# MotorControl.net
KiCad netlist of a schematic drawn in Altium Designer
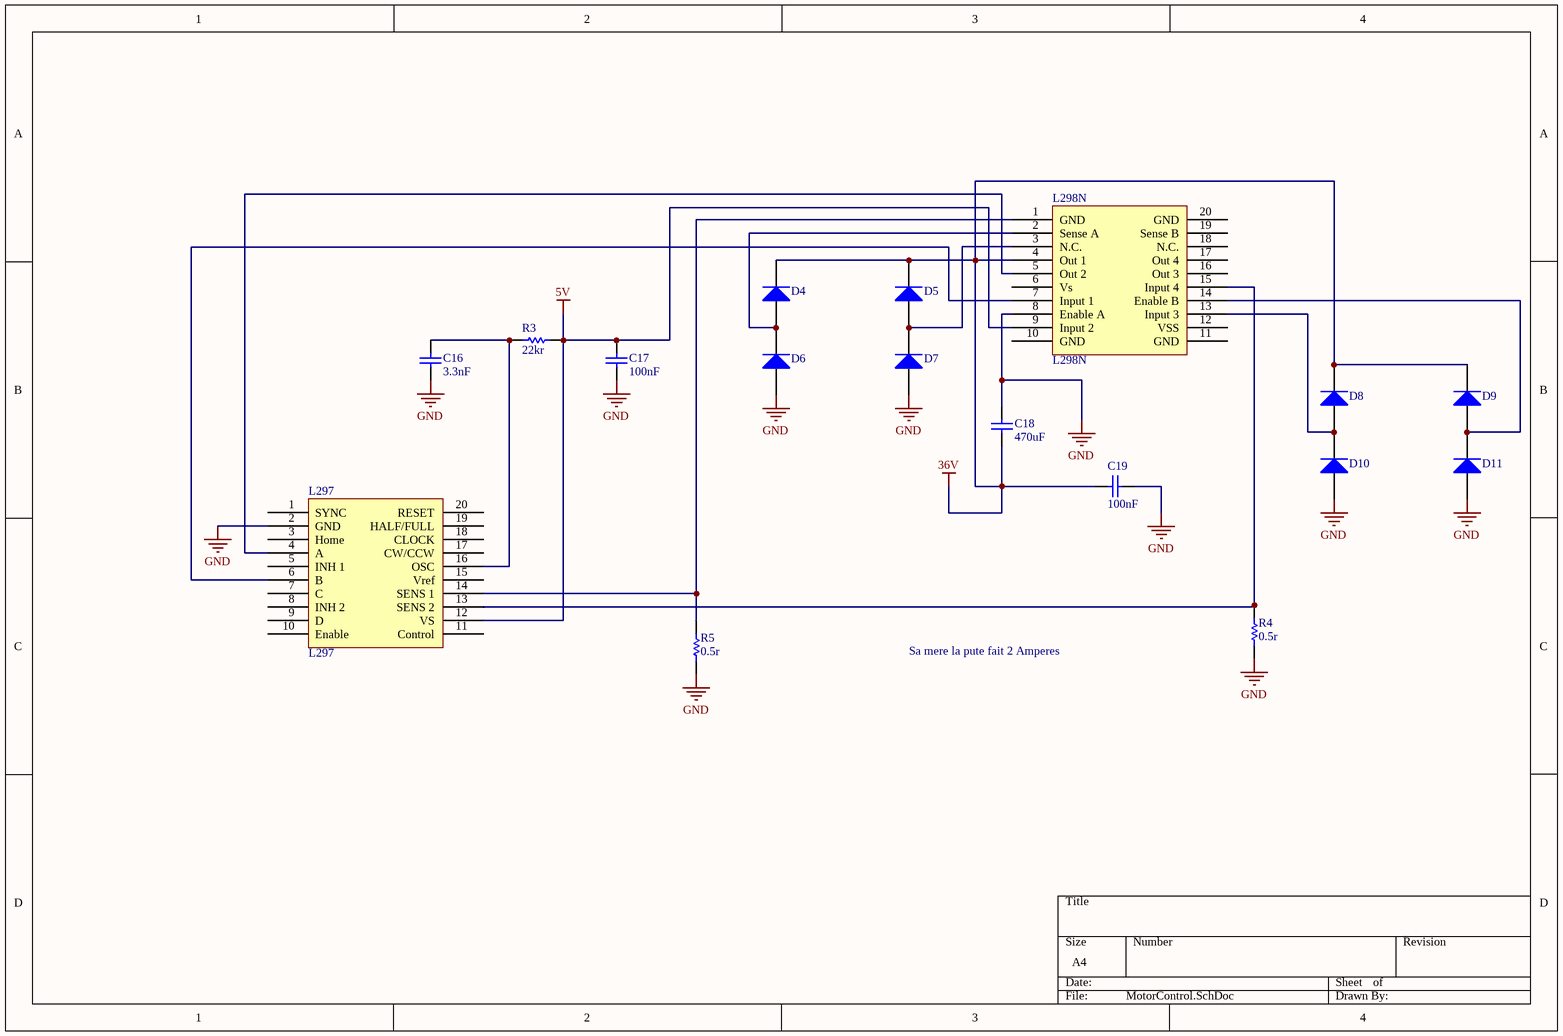
[diagram p0: MotorControl.SchDoc]

(export (version "E")
  (design (tool "Eeschema 10.0.6"))
  (components
    (comp (ref "C16")
      (value "3.3nF")
      (footprint "CAPC2012N")
      (description "Capacitor")
      (fields (field (name "PUBLISHER") "Altium Limited"))
      (libsource (lib "Miscellaneous Devices") (part "Cap"))
    )
    (comp (ref "C17")
      (value "100nF")
      (footprint "CAPC2012N")
      (description "Capacitor")
      (fields (field (name "PUBLISHER") "Altium Limited"))
      (libsource (lib "Miscellaneous Devices") (part "Cap"))
    )
    (comp (ref "C18")
      (value "470uF")
      (footprint "CAPC2012N")
      (description "Capacitor")
      (fields (field (name "PUBLISHER") "Altium Limited"))
      (libsource (lib "Miscellaneous Devices") (part "Cap"))
    )
    (comp (ref "C19")
      (value "100nF")
      (footprint "CAPC2012N")
      (description "Capacitor")
      (fields (field (name "PUBLISHER") "Altium Limited"))
      (libsource (lib "Miscellaneous Devices") (part "Cap"))
    )
    (comp (ref "D4")
      (value "~")
      (footprint "SMC")
      (description "Default Diode")
      (fields (field (name "PUBLISHER") "Altium Limited"))
      (libsource (lib "Miscellaneous Devices") (part "Diode"))
    )
    (comp (ref "D5")
      (value "~")
      (footprint "SMC")
      (description "Default Diode")
      (fields (field (name "PUBLISHER") "Altium Limited"))
      (libsource (lib "Miscellaneous Devices") (part "Diode"))
    )
    (comp (ref "D6")
      (value "~")
      (footprint "SMC")
      (description "Default Diode")
      (fields (field (name "PUBLISHER") "Altium Limited"))
      (libsource (lib "Miscellaneous Devices") (part "Diode"))
    )
    (comp (ref "D7")
      (value "~")
      (footprint "SMC")
      (description "Default Diode")
      (fields (field (name "PUBLISHER") "Altium Limited"))
      (libsource (lib "Miscellaneous Devices") (part "Diode"))
    )
    (comp (ref "D8")
      (value "~")
      (footprint "SMC")
      (description "Default Diode")
      (fields (field (name "PUBLISHER") "Altium Limited"))
      (libsource (lib "Miscellaneous Devices") (part "Diode"))
    )
    (comp (ref "D9")
      (value "~")
      (footprint "SMC")
      (description "Default Diode")
      (fields (field (name "PUBLISHER") "Altium Limited"))
      (libsource (lib "Miscellaneous Devices") (part "Diode"))
    )
    (comp (ref "D10")
      (value "~")
      (footprint "SMC")
      (description "Default Diode")
      (fields (field (name "PUBLISHER") "Altium Limited"))
      (libsource (lib "Miscellaneous Devices") (part "Diode"))
    )
    (comp (ref "D11")
      (value "~")
      (footprint "SMC")
      (description "Default Diode")
      (fields (field (name "PUBLISHER") "Altium Limited"))
      (libsource (lib "Miscellaneous Devices") (part "Diode"))
    )
    (comp (ref "L297") (value "L297") (libsource (lib "TP2") (part "L297")))
    (comp (ref "L298N") (value "L298N") (libsource (lib "TP2") (part "L298N")))
    (comp (ref "R3")
      (value "22kr")
      (footprint "AXIAL-0.3")
      (description "Resistor")
      (fields (field (name "PUBLISHER") "Altium Limited"))
      (libsource (lib "Miscellaneous Devices") (part "Res1"))
    )
    (comp (ref "R4")
      (value "0.5r")
      (footprint "AXIAL-0.3")
      (description "Resistor")
      (fields (field (name "PUBLISHER") "Altium Limited"))
      (libsource (lib "Miscellaneous Devices") (part "Res1"))
    )
    (comp (ref "R5")
      (value "0.5r")
      (footprint "AXIAL-0.3")
      (description "Resistor")
      (fields (field (name "PUBLISHER") "Altium Limited"))
      (libsource (lib "Miscellaneous Devices") (part "Res1"))
    )
  )
  (nets
    (net (code "1") (name "5V") (class "Default")
      (node (ref "C17") (pin "2") (pinfunction "2_2") (pintype "passive"))
      (node (ref "L297") (pin "12") (pinfunction "VS_12") (pintype "power_in"))
      (node (ref "L298N") (pin "9") (pinfunction "Input_2_9") (pintype "power_in"))
      (node (ref "R3") (pin "1") (pinfunction "1_1") (pintype "passive"))
    )
    (net (code "2") (name "36V") (class "Default")
      (node (ref "C18") (pin "2") (pinfunction "2_2") (pintype "passive"))
      (node (ref "C19") (pin "2") (pinfunction "2_2") (pintype "passive"))
      (node (ref "D4") (pin "2") (pinfunction "K_2") (pintype "passive"))
      (node (ref "D5") (pin "2") (pinfunction "K_2") (pintype "passive"))
      (node (ref "D8") (pin "2") (pinfunction "K_2") (pintype "passive"))
      (node (ref "D9") (pin "2") (pinfunction "K_2") (pintype "passive"))
      (node (ref "L298N") (pin "4") (pinfunction "Out_1_4") (pintype "power_in"))
    )
    (net (code "3") (name "GND") (class "Default")
      (node (ref "C16") (pin "1") (pinfunction "1_1") (pintype "passive"))
      (node (ref "C17") (pin "1") (pinfunction "1_1") (pintype "passive"))
      (node (ref "C18") (pin "1") (pinfunction "1_1") (pintype "passive"))
      (node (ref "C19") (pin "1") (pinfunction "1_1") (pintype "passive"))
      (node (ref "D10") (pin "1") (pinfunction "A_1") (pintype "passive"))
      (node (ref "D11") (pin "1") (pinfunction "A_1") (pintype "passive"))
      (node (ref "D6") (pin "1") (pinfunction "A_1") (pintype "passive"))
      (node (ref "D7") (pin "1") (pinfunction "A_1") (pintype "passive"))
      (node (ref "L297") (pin "2") (pinfunction "GND_2") (pintype "power_in"))
      (node (ref "L298N") (pin "8") (pinfunction "Enable_A_8") (pintype "power_in"))
      (node (ref "R4") (pin "2") (pinfunction "2_2") (pintype "passive"))
      (node (ref "R5") (pin "2") (pinfunction "2_2") (pintype "passive"))
    )
    (net (code "4") (name "Net-(D4-A)") (class "Default")
      (node (ref "D4") (pin "1") (pinfunction "A_1") (pintype "passive"))
      (node (ref "D6") (pin "2") (pinfunction "K_2") (pintype "passive"))
      (node (ref "L298N") (pin "2") (pinfunction "Sense_A_2") (pintype "power_in"))
    )
    (net (code "5") (name "Net-(D5-A)") (class "Default")
      (node (ref "D5") (pin "1") (pinfunction "A_1") (pintype "passive"))
      (node (ref "D7") (pin "2") (pinfunction "K_2") (pintype "passive"))
      (node (ref "L298N") (pin "3") (pinfunction "N.C._3") (pintype "power_in"))
    )
    (net (code "6") (name "Net-(D10-K)") (class "Default")
      (node (ref "D10") (pin "2") (pinfunction "K_2") (pintype "passive"))
      (node (ref "D8") (pin "1") (pinfunction "A_1") (pintype "passive"))
      (node (ref "L298N") (pin "13") (pinfunction "Input_3_13") (pintype "power_in"))
    )
    (net (code "7") (name "Net-(D11-K)") (class "Default")
      (node (ref "D11") (pin "2") (pinfunction "K_2") (pintype "passive"))
      (node (ref "D9") (pin "1") (pinfunction "A_1") (pintype "passive"))
      (node (ref "L298N") (pin "14") (pinfunction "Enable_B_14") (pintype "power_in"))
    )
    (net (code "8") (name "Net-(L297-A)") (class "Default")
      (node (ref "L297") (pin "4") (pinfunction "A_4") (pintype "power_in"))
      (node (ref "L298N") (pin "5") (pinfunction "Out_2_5") (pintype "power_in"))
    )
    (net (code "9") (name "Net-(L297-B)") (class "Default")
      (node (ref "L297") (pin "6") (pinfunction "B_6") (pintype "power_in"))
      (node (ref "L298N") (pin "7") (pinfunction "Input_1_7") (pintype "power_in"))
    )
    (net (code "10") (name "Net-(L297-OSC)") (class "Default")
      (node (ref "C16") (pin "2") (pinfunction "2_2") (pintype "passive"))
      (node (ref "L297") (pin "16") (pinfunction "OSC_16") (pintype "power_in"))
      (node (ref "R3") (pin "2") (pinfunction "2_2") (pintype "passive"))
    )
    (net (code "11") (name "Net-(L297-SENS_1)") (class "Default")
      (node (ref "L297") (pin "14") (pinfunction "SENS_1_14") (pintype "power_in"))
      (node (ref "L298N") (pin "1") (pinfunction "GND_1") (pintype "power_in"))
      (node (ref "R5") (pin "1") (pinfunction "1_1") (pintype "passive"))
    )
    (net (code "12") (name "Net-(L297-SENS_2)") (class "Default")
      (node (ref "L297") (pin "13") (pinfunction "SENS_2_13") (pintype "power_in"))
      (node (ref "L298N") (pin "15") (pinfunction "Input_4_15") (pintype "power_in"))
      (node (ref "R4") (pin "1") (pinfunction "1_1") (pintype "passive"))
    )
    (net (code "13") (name "unconnected-(L297-C-Pad7)") (class "Default")
      (node (ref "L297") (pin "7") (pinfunction "C_7") (pintype "power_in"))
    )
    (net (code "14") (name "unconnected-(L297-CLOCK-Pad18)") (class "Default")
      (node (ref "L297") (pin "18") (pinfunction "CLOCK_18") (pintype "power_in"))
    )
    (net (code "15") (name "unconnected-(L297-CW{slash}CCW-Pad17)") (class "Default")
      (node (ref "L297") (pin "17") (pinfunction "CW/CCW_17") (pintype "power_in"))
    )
    (net (code "16") (name "unconnected-(L297-Control-Pad11)") (class "Default")
      (node (ref "L297") (pin "11") (pinfunction "Control_11") (pintype "power_in"))
    )
    (net (code "17") (name "unconnected-(L297-D-Pad9)") (class "Default")
      (node (ref "L297") (pin "9") (pinfunction "D_9") (pintype "power_in"))
    )
    (net (code "18") (name "unconnected-(L297-Enable-Pad10)") (class "Default")
      (node (ref "L297") (pin "10") (pinfunction "Enable_10") (pintype "power_in"))
    )
    (net (code "19") (name "unconnected-(L297-HALF{slash}FULL-Pad19)") (class "Default")
      (node (ref "L297") (pin "19") (pinfunction "HALF/FULL_19") (pintype "power_in"))
    )
    (net (code "20") (name "unconnected-(L297-Home-Pad3)") (class "Default")
      (node (ref "L297") (pin "3") (pinfunction "Home_3") (pintype "power_in"))
    )
    (net (code "21") (name "unconnected-(L297-INH_1-Pad5)") (class "Default")
      (node (ref "L297") (pin "5") (pinfunction "INH_1_5") (pintype "power_in"))
    )
    (net (code "22") (name "unconnected-(L297-INH_2-Pad8)") (class "Default")
      (node (ref "L297") (pin "8") (pinfunction "INH_2_8") (pintype "power_in"))
    )
    (net (code "23") (name "unconnected-(L297-RESET-Pad20)") (class "Default")
      (node (ref "L297") (pin "20") (pinfunction "RESET_20") (pintype "power_in"))
    )
    (net (code "24") (name "unconnected-(L297-SYNC-Pad1)") (class "Default")
      (node (ref "L297") (pin "1") (pinfunction "SYNC_1") (pintype "power_in"))
    )
    (net (code "25") (name "unconnected-(L297-Vref-Pad15)") (class "Default")
      (node (ref "L297") (pin "15") (pinfunction "Vref_15") (pintype "power_in"))
    )
    (net (code "26") (name "unconnected-(L298N-GND-Pad10)") (class "Default")
      (node (ref "L298N") (pin "10") (pinfunction "GND_10") (pintype "power_in"))
    )
    (net (code "27") (name "unconnected-(L298N-GND-Pad11)") (class "Default")
      (node (ref "L298N") (pin "11") (pinfunction "GND_11") (pintype "power_in"))
    )
    (net (code "28") (name "unconnected-(L298N-GND-Pad20)") (class "Default")
      (node (ref "L298N") (pin "20") (pinfunction "GND_20") (pintype "power_in"))
    )
    (net (code "29") (name "unconnected-(L298N-N.C.-Pad18)") (class "Default")
      (node (ref "L298N") (pin "18") (pinfunction "N.C._18") (pintype "power_in"))
    )
    (net (code "30") (name "unconnected-(L298N-Out_3-Pad16)") (class "Default")
      (node (ref "L298N") (pin "16") (pinfunction "Out_3_16") (pintype "power_in"))
    )
    (net (code "31") (name "unconnected-(L298N-Out_4-Pad17)") (class "Default")
      (node (ref "L298N") (pin "17") (pinfunction "Out_4_17") (pintype "power_in"))
    )
    (net (code "32") (name "unconnected-(L298N-Sense_B-Pad19)") (class "Default")
      (node (ref "L298N") (pin "19") (pinfunction "Sense_B_19") (pintype "power_in"))
    )
    (net (code "33") (name "unconnected-(L298N-VSS-Pad12)") (class "Default")
      (node (ref "L298N") (pin "12") (pinfunction "VSS_12") (pintype "power_in"))
    )
    (net (code "34") (name "unconnected-(L298N-Vs-Pad6)") (class "Default")
      (node (ref "L298N") (pin "6") (pinfunction "Vs_6") (pintype "power_in"))
    )
  )
)
